# ArbPwrBoost_P6.net
KiCad netlist of a schematic drawn in Altium Designer
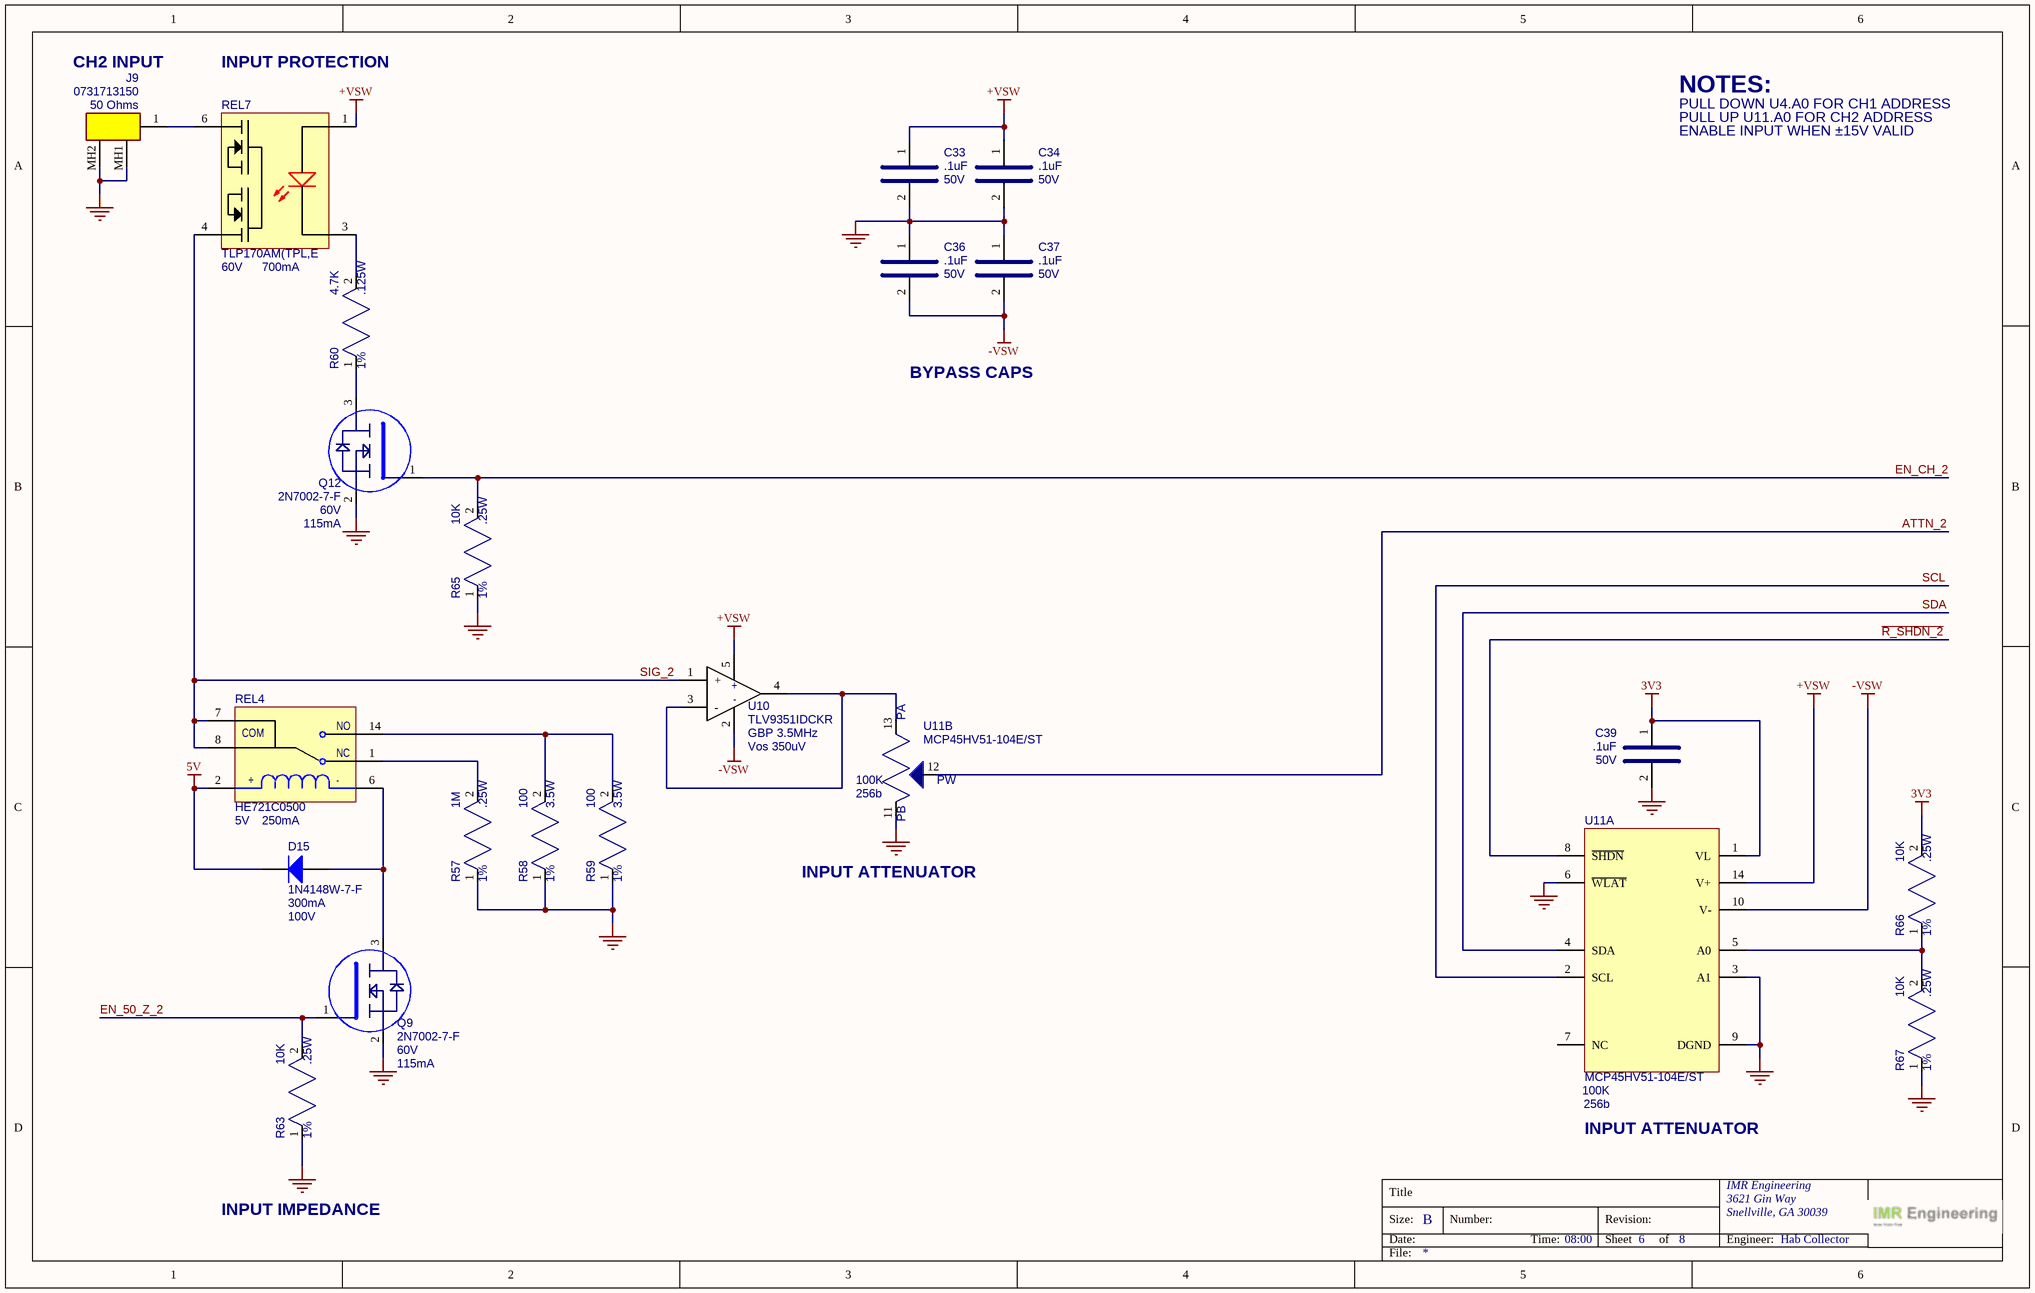
[diagram p0: ArbPwrBoost_P6.SchDoc]

(export (version "E")
  (design (tool "Eeschema 10.0.6"))
  (components
    (comp (ref "C33")
      (value ".1uF")
      (footprint "CAP_0805")
      (description "CAP CER 0.1UF 50V X7R 0805")
      (fields
        (field (name "MFG") "KYOCERA AVX")
        (field (name "VOLTAGE") "50V")
        (field (name "Comment") "KGM21NR71H104KT")
      )
      (libsource (lib "IMR_LIB_SCH_R2") (part "CAP_SMD_0.1UF_50V_0805"))
    )
    (comp (ref "C34")
      (value ".1uF")
      (footprint "CAP_0805")
      (description "CAP CER 0.1UF 50V X7R 0805")
      (fields
        (field (name "MFG") "KYOCERA AVX")
        (field (name "VOLTAGE") "50V")
        (field (name "Comment") "KGM21NR71H104KT")
      )
      (libsource (lib "IMR_LIB_SCH_R2") (part "CAP_SMD_0.1UF_50V_0805"))
    )
    (comp (ref "C36")
      (value ".1uF")
      (footprint "CAP_0805")
      (description "CAP CER 0.1UF 50V X7R 0805")
      (fields
        (field (name "MFG") "KYOCERA AVX")
        (field (name "VOLTAGE") "50V")
        (field (name "Comment") "KGM21NR71H104KT")
      )
      (libsource (lib "IMR_LIB_SCH_R2") (part "CAP_SMD_0.1UF_50V_0805"))
    )
    (comp (ref "C37")
      (value ".1uF")
      (footprint "CAP_0805")
      (description "CAP CER 0.1UF 50V X7R 0805")
      (fields
        (field (name "MFG") "KYOCERA AVX")
        (field (name "VOLTAGE") "50V")
        (field (name "Comment") "KGM21NR71H104KT")
      )
      (libsource (lib "IMR_LIB_SCH_R2") (part "CAP_SMD_0.1UF_50V_0805"))
    )
    (comp (ref "C39")
      (value ".1uF")
      (footprint "CAP_0805")
      (description "CAP CER 0.1UF 50V X7R 0805")
      (fields
        (field (name "MFG") "KYOCERA AVX")
        (field (name "VOLTAGE") "50V")
        (field (name "Comment") "KGM21NR71H104KT")
      )
      (libsource (lib "IMR_LIB_SCH_R2") (part "CAP_SMD_0.1UF_50V_0805"))
    )
    (comp (ref "D15")
      (value "100V")
      (footprint "SOD123")
      (description "RELAY REED SPDT 250MA 5V")
      (fields
        (field (name "MFG") "Diodes Inc")
        (field (name "MFG_PN") "1N4148W-7-F")
        (field (name "CURRENT") "300mA")
        (field (name "Comment") "1N4148W-7-F")
      )
      (libsource (lib "IMR_LIB_SCH_R2") (part "DIODE_1N4148W-7-F"))
    )
    (comp (ref "J9")
      (value "50 Ohms")
      (footprint "731713150")
      (description "CONN BNC RCPT R/A 50 OHM PCB")
      (fields
        (field (name "MFG") "Molex")
        (field (name "MFG_PN") "0731713150")
        (field (name "Comment") "0731713150")
      )
      (libsource (lib "IMR_LIB_SCH_R2") (part "CONN_MOLEX_0731713150"))
    )
    (comp (ref "Q9")
      (value "60V")
      (footprint "SOT-23")
      (description "MOSFET N-CH 60V 115MA SOT23-3")
      (fields
        (field (name "MFG") "Diodes Inc")
        (field (name "MFG_PN") "2N7002-7-F")
        (field (name "CURRENT") "115mA")
        (field (name "Comment") "2N7002-7-F")
      )
      (libsource (lib "") (part "MOSFET_NCH_2N7002-7-F_1"))
    )
    (comp (ref "Q12")
      (value "60V")
      (footprint "SOT-23")
      (description "MOSFET N-CH 60V 115MA SOT23-3")
      (fields
        (field (name "MFG") "Diodes Inc")
        (field (name "MFG_PN") "2N7002-7-F")
        (field (name "CURRENT") "115mA")
        (field (name "Comment") "2N7002-7-F")
      )
      (libsource (lib "IMR_LIB_SCH_R2") (part "MOSFET_NCH_2N7002-7-F"))
    )
    (comp (ref "R57")
      (value "1M")
      (footprint "RES_0805")
      (description "RES SMD 1K OHM 1% 1/4W 0805")
      (fields
        (field (name "MFG") "Yageo")
        (field (name "POWER") ".25W")
        (field (name "TOLERANCE") "1%")
        (field (name "Comment") "RC0805FR-7W1ML")
      )
      (libsource (lib "IMR_LIB_SCH_R2") (part "RES_SMD_1M_0805_1/4W_1%"))
    )
    (comp (ref "R58")
      (value "100")
      (footprint "RES_2512")
      (description "RES SMD 100 OHM 1% 3.5W 2512")
      (fields
        (field (name "MFG") "Ohmite")
        (field (name "POWER") "3.5W")
        (field (name "TOLERANCE") "1%")
        (field (name "Comment") "ALN2512F100RE-1")
      )
      (libsource (lib "IMR_LIB_SCH_R2") (part "RES_SMD_100_0805_3.5W_1%"))
    )
    (comp (ref "R59")
      (value "100")
      (footprint "RES_2512")
      (description "RES SMD 100 OHM 1% 3.5W 2512")
      (fields
        (field (name "MFG") "Ohmite")
        (field (name "POWER") "3.5W")
        (field (name "TOLERANCE") "1%")
        (field (name "Comment") "ALN2512F100RE-1")
      )
      (libsource (lib "IMR_LIB_SCH_R2") (part "RES_SMD_100_0805_3.5W_1%"))
    )
    (comp (ref "R60")
      (value "4.7K")
      (footprint "RES_0805")
      (description "RES SMD 4.7K OHM 1% 1/8W 0805")
      (fields
        (field (name "MFG") "Yageo")
        (field (name "POWER") ".125W")
        (field (name "TOLERANCE") "1%")
        (field (name "Comment") "RC0805FR-134K7L")
      )
      (libsource (lib "IMR_LIB_SCH_R2") (part "RES_SMD_4.7K_0805_1/8W_1%"))
    )
    (comp (ref "R63")
      (value "10K")
      (footprint "RES_0805")
      (description "RES SMD 10K OHM 1% 1/4W 0805")
      (fields
        (field (name "MFG") "Yageo")
        (field (name "POWER") ".25W")
        (field (name "TOLERANCE") "1%")
        (field (name "Comment") "RC0805FR-7W10KL")
      )
      (libsource (lib "IMR_LIB_SCH_R2") (part "RES_SMD_10K_0805_1/4W_1%"))
    )
    (comp (ref "R65")
      (value "10K")
      (footprint "RES_0805")
      (description "RES SMD 10K OHM 1% 1/4W 0805")
      (fields
        (field (name "MFG") "Yageo")
        (field (name "POWER") ".25W")
        (field (name "TOLERANCE") "1%")
        (field (name "Comment") "RC0805FR-7W10KL")
      )
      (libsource (lib "IMR_LIB_SCH_R2") (part "RES_SMD_10K_0805_1/4W_1%"))
    )
    (comp (ref "R66")
      (value "10K")
      (footprint "RES_0805")
      (description "RES SMD 10K OHM 1% 1/4W 0805")
      (fields
        (field (name "MFG") "Yageo")
        (field (name "POWER") ".25W")
        (field (name "TOLERANCE") "1%")
        (field (name "Comment") "RC0805FR-7W10KL")
      )
      (libsource (lib "IMR_LIB_SCH_R2") (part "RES_SMD_10K_0805_1/4W_1%"))
    )
    (comp (ref "R67")
      (value "10K")
      (footprint "RES_0805")
      (description "RES SMD 10K OHM 1% 1/4W 0805")
      (fields
        (field (name "MFG") "Yageo")
        (field (name "POWER") ".25W")
        (field (name "TOLERANCE") "1%")
        (field (name "Comment") "RC0805FR-7W10KL")
      )
      (libsource (lib "IMR_LIB_SCH_R2") (part "RES_SMD_10K_0805_1/4W_1%"))
    )
    (comp (ref "REL4")
      (value "5V")
      (footprint "HE700")
      (description "RELAY REED SPDT 250MA 5V")
      (fields
        (field (name "MFG") "Littlefuse")
        (field (name "MFG_PN") "HE721C0500")
        (field (name "CURRENT") "250mA")
        (field (name "Comment") "HE721C0500")
      )
      (libsource (lib "IMR_LIB_SCH_R2") (part "RELAY_HE721C0500"))
    )
    (comp (ref "REL7")
      (value "60V")
      (footprint "SOP-6")
      (description "SSR RELAY SPST-NO 700MA 0-60V")
      (fields
        (field (name "MFG") "Toshiba")
        (field (name "MFG_PN") "TLP170AM(TPL,E")
        (field (name "CURRENT") "700mA")
        (field (name "Comment") "TLP170AM(TPL,E")
      )
      (libsource (lib "IMR_LIB_SCH_R2") (part "RELAY_TLP170AM(TPL,E"))
    )
    (comp (ref "U10")
      (value "GBP 3.5MHz")
      (footprint "SOT-353")
      (description "IC OPAMP GP 3.5MHZ 350uV C70-5")
      (fields
        (field (name "MFG") "Texas Instruments")
        (field (name "MFG_PN") "TLV9351IDCKR")
        (field (name "VOS") "Vos 350uV")
        (field (name "Comment") "TLV9351IDCKR")
      )
      (libsource (lib "IMR_LIB_SCH_R2") (part "OPAMP_TLV9351IDCKR"))
    )
    (comp (ref "U11")
      (value "100K")
      (footprint "TSSOP-14")
      (description "IC DGT POT 100KOHM 256TP 14TSSOP")
      (fields
        (field (name "MFG") "Microchip")
        (field (name "MFG_PN") "MCP45HV51-104E/ST")
        (field (name "TAP") "256b")
        (field (name "Comment") "MCP45HV51-104E/ST")
      )
      (libsource (lib "IMR_LIB_SCH_R2") (part "IC_MCP45HV51-104E/ST"))
    )
  )
  (nets
    (net (code "1") (name "+VSW") (class "Default")
      (node (ref "C33") (pin "1") (pinfunction "1_1") (pintype "passive"))
      (node (ref "C34") (pin "1") (pinfunction "1_1") (pintype "passive"))
      (node (ref "REL7") (pin "1") (pinfunction "1_1") (pintype "passive"))
      (node (ref "U10") (pin "5") (pintype "passive"))
      (node (ref "U11") (pin "14") (pinfunction "V+_14") (pintype "passive"))
    )
    (net (code "2") (name "-VSW") (class "Default")
      (node (ref "C36") (pin "2") (pinfunction "2_2") (pintype "passive"))
      (node (ref "C37") (pin "2") (pinfunction "2_2") (pintype "passive"))
      (node (ref "U10") (pin "2") (pintype "passive"))
      (node (ref "U11") (pin "10") (pinfunction "V-_10") (pintype "passive"))
    )
    (net (code "3") (name "/ATTN_2") (class "Default")
      (node (ref "U11") (pin "12") (pinfunction "PW0_12") (pintype "passive"))
    )
    (net (code "4") (name "/EN_50_Z_2") (class "Default")
      (node (ref "Q9") (pin "1") (pinfunction "B_1") (pintype "passive"))
      (node (ref "R63") (pin "2") (pinfunction "2_2") (pintype "passive"))
    )
    (net (code "5") (name "/EN_CH_2") (class "Default")
      (node (ref "Q12") (pin "1") (pinfunction "B_1") (pintype "passive"))
      (node (ref "R65") (pin "2") (pinfunction "2_2") (pintype "passive"))
    )
    (net (code "6") (name "/SCL") (class "Default")
      (node (ref "U11") (pin "2") (pinfunction "SCL_2") (pintype "passive"))
    )
    (net (code "7") (name "/SDA") (class "Default")
      (node (ref "U11") (pin "4") (pinfunction "SDA_4") (pintype "passive"))
    )
    (net (code "8") (name "/SIG_2") (class "Default")
      (node (ref "REL4") (pin "7") (pinfunction "COM_7") (pintype "passive"))
      (node (ref "REL4") (pin "8") (pinfunction "COM_8") (pintype "passive"))
      (node (ref "REL7") (pin "4") (pinfunction "4_4") (pintype "passive"))
      (node (ref "U10") (pin "1") (pinfunction "+_1") (pintype "passive"))
    )
    (net (code "9") (name "/~{R_SHDN_2}") (class "Default")
      (node (ref "U11") (pin "8") (pinfunction "~{SHDN}_8") (pintype "passive"))
    )
    (net (code "10") (name "3V3") (class "Default")
      (node (ref "C39") (pin "1") (pinfunction "1_1") (pintype "passive"))
      (node (ref "R66") (pin "2") (pinfunction "2_2") (pintype "passive"))
      (node (ref "U11") (pin "1") (pinfunction "VL_1") (pintype "passive"))
    )
    (net (code "11") (name "5V") (class "Default")
      (node (ref "D15") (pin "2") (pinfunction "K_2") (pintype "passive"))
      (node (ref "REL4") (pin "2") (pintype "passive"))
    )
    (net (code "12") (name "GND") (class "Default")
      (node (ref "C33") (pin "2") (pinfunction "2_2") (pintype "passive"))
      (node (ref "C34") (pin "2") (pinfunction "2_2") (pintype "passive"))
      (node (ref "C36") (pin "1") (pinfunction "1_1") (pintype "passive"))
      (node (ref "C37") (pin "1") (pinfunction "1_1") (pintype "passive"))
      (node (ref "C39") (pin "2") (pinfunction "2_2") (pintype "passive"))
      (node (ref "J9") (pin "MH1") (pintype "passive"))
      (node (ref "J9") (pin "MH2") (pintype "passive"))
      (node (ref "Q12") (pin "2") (pinfunction "E_2") (pintype "passive"))
      (node (ref "Q9") (pin "2") (pinfunction "E_2") (pintype "passive"))
      (node (ref "R57") (pin "1") (pinfunction "1_1") (pintype "passive"))
      (node (ref "R58") (pin "1") (pinfunction "1_1") (pintype "passive"))
      (node (ref "R59") (pin "1") (pinfunction "1_1") (pintype "passive"))
      (node (ref "R63") (pin "1") (pinfunction "1_1") (pintype "passive"))
      (node (ref "R65") (pin "1") (pinfunction "1_1") (pintype "passive"))
      (node (ref "R67") (pin "1") (pinfunction "1_1") (pintype "passive"))
      (node (ref "U11") (pin "11") (pinfunction "PB0_11") (pintype "passive"))
      (node (ref "U11") (pin "3") (pinfunction "A1_3") (pintype "passive"))
      (node (ref "U11") (pin "6") (pinfunction "~{WLAT}_6") (pintype "passive"))
      (node (ref "U11") (pin "9") (pinfunction "DGND_9") (pintype "passive"))
    )
    (net (code "13") (name "Net-(D15-A)") (class "Default")
      (node (ref "D15") (pin "1") (pinfunction "A_1") (pintype "passive"))
      (node (ref "Q9") (pin "3") (pinfunction "C_3") (pintype "passive"))
      (node (ref "REL4") (pin "6") (pintype "passive"))
    )
    (net (code "14") (name "Net-(J9-Pad1)") (class "Default")
      (node (ref "J9") (pin "1") (pintype "passive"))
      (node (ref "REL7") (pin "6") (pinfunction "6_6") (pintype "passive"))
    )
    (net (code "15") (name "Net-(Q12-C)") (class "Default")
      (node (ref "Q12") (pin "3") (pinfunction "C_3") (pintype "passive"))
      (node (ref "R60") (pin "1") (pinfunction "1_1") (pintype "passive"))
    )
    (net (code "16") (name "Net-(R60-Pad2)") (class "Default")
      (node (ref "R60") (pin "2") (pinfunction "2_2") (pintype "passive"))
      (node (ref "REL7") (pin "3") (pinfunction "3_3") (pintype "passive"))
    )
    (net (code "17") (name "Net-(REL4-NC)") (class "Default")
      (node (ref "R57") (pin "2") (pinfunction "2_2") (pintype "passive"))
      (node (ref "REL4") (pin "1") (pinfunction "NC_1") (pintype "passive"))
    )
    (net (code "18") (name "Net-(REL4-NO)") (class "Default")
      (node (ref "R58") (pin "2") (pinfunction "2_2") (pintype "passive"))
      (node (ref "R59") (pin "2") (pinfunction "2_2") (pintype "passive"))
      (node (ref "REL4") (pin "14") (pinfunction "NO_14") (pintype "passive"))
    )
    (net (code "19") (name "Net-(U10--)") (class "Default")
      (node (ref "U10") (pin "3") (pinfunction "-_3") (pintype "passive"))
      (node (ref "U10") (pin "4") (pintype "passive"))
      (node (ref "U11") (pin "13") (pinfunction "PA_13") (pintype "passive"))
    )
    (net (code "20") (name "Net-(U11A-A0)") (class "Default")
      (node (ref "R66") (pin "1") (pinfunction "1_1") (pintype "passive"))
      (node (ref "R67") (pin "2") (pinfunction "2_2") (pintype "passive"))
      (node (ref "U11") (pin "5") (pinfunction "A0_5") (pintype "passive"))
    )
    (net (code "21") (name "unconnected-(U11A-NC-Pad7)") (class "Default")
      (node (ref "U11") (pin "7") (pinfunction "NC_7") (pintype "passive"))
    )
  )
)
